# ATmegaIntOscillator.net
KiCad netlist of a schematic drawn in EAGLE
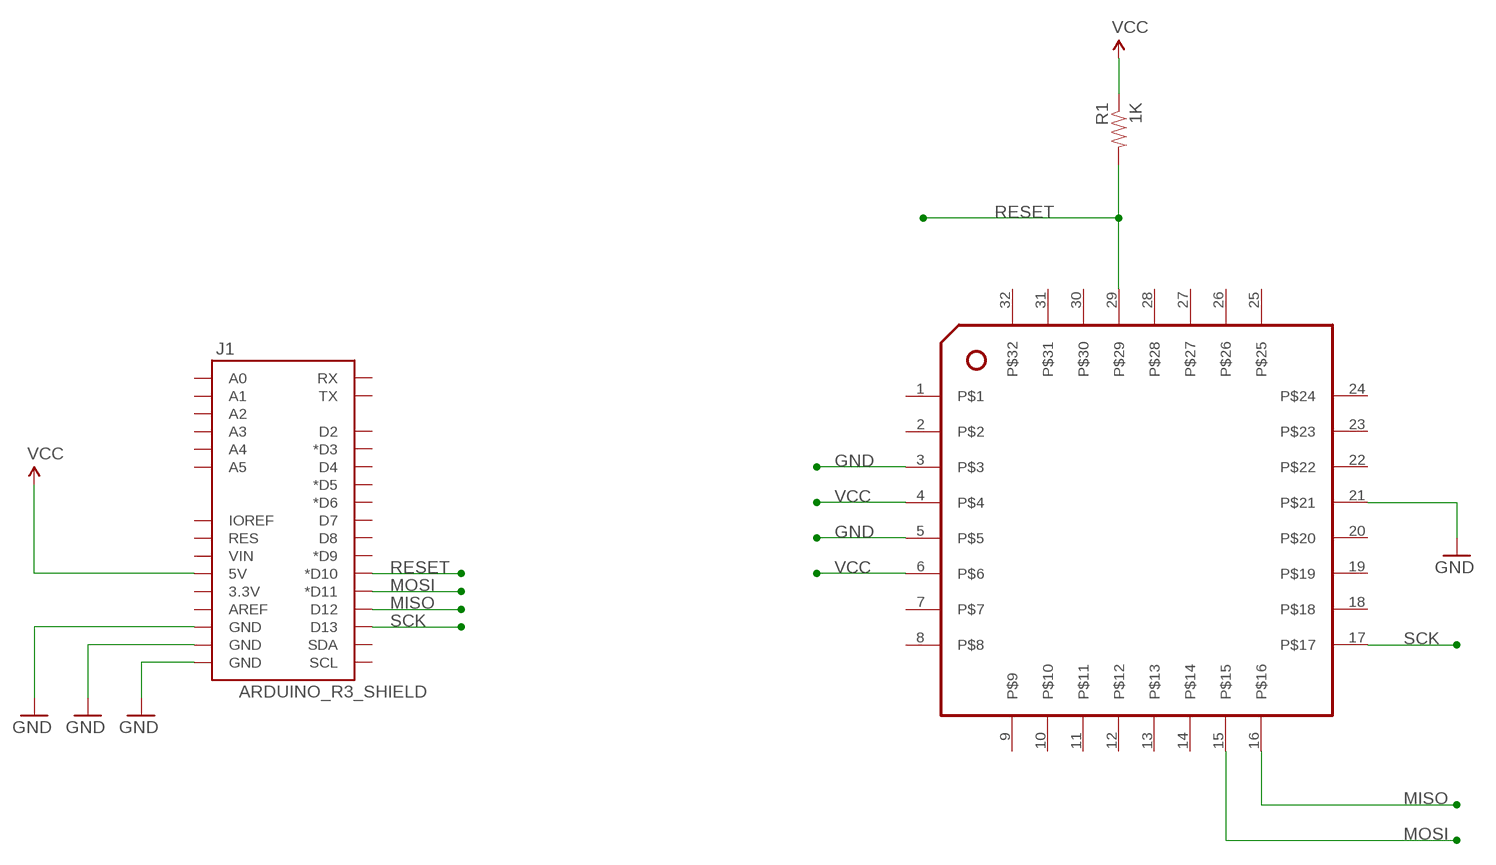
[diagram p0: schematic, sheet 1]

(export (version "E")
  (design (tool "Eeschema 10.0.6"))
  (components
    (comp (ref "J1")
      (value "ARDUINO_R3_SHIELD")
      (footprint "eagle-import:UNO_R3_SHIELD")
      (libsource (lib "eagle-import") (part "ARDUINO_R3_SHIELD"))
    )
    (comp (ref "R1")
      (value "1K")
      (footprint "eagle-import:AXIAL-0.3")
      (libsource (lib "eagle-import") (part "1KOHM-1/4W-1%(PTH)"))
    )
    (comp (ref "U$1")
      (value "ATMEGA-TQFP-BREAKOUT")
      (footprint "eagle-import:TQFP32-BREAKOUT")
      (libsource (lib "eagle-import") (part "ATMEGA-TQFP-BREAKOUT"))
    )
  )
  (nets
    (net (code "1") (name "/MISO") (class "Default")
      (node (ref "J1") (pin "D12") (pinfunction "D12_D12") (pintype "bidirectional"))
      (node (ref "U$1") (pin "16") (pinfunction "P$16_16") (pintype "bidirectional"))
    )
    (net (code "2") (name "/MOSI") (class "Default")
      (node (ref "J1") (pin "D11") (pinfunction "*D11_D11") (pintype "bidirectional"))
      (node (ref "U$1") (pin "15") (pinfunction "P$15_15") (pintype "bidirectional"))
    )
    (net (code "3") (name "/RESET") (class "Default")
      (node (ref "J1") (pin "D10") (pinfunction "*D10_D10") (pintype "bidirectional"))
      (node (ref "R1") (pin "P$2") (pinfunction "2_P$2") (pintype "passive"))
      (node (ref "U$1") (pin "29") (pinfunction "P$29_29") (pintype "bidirectional"))
    )
    (net (code "4") (name "/SCK") (class "Default")
      (node (ref "J1") (pin "D13") (pinfunction "D13_D13") (pintype "bidirectional"))
      (node (ref "U$1") (pin "17") (pinfunction "P$17_17") (pintype "bidirectional"))
    )
    (net (code "5") (name "GND") (class "Default")
      (node (ref "J1") (pin "GND@0") (pinfunction "GND_GND@0") (pintype "bidirectional"))
      (node (ref "J1") (pin "GND@1") (pinfunction "GND_GND@1") (pintype "bidirectional"))
      (node (ref "J1") (pin "GND@2") (pinfunction "GND_GND@2") (pintype "bidirectional"))
      (node (ref "U$1") (pin "21") (pinfunction "P$21_21") (pintype "bidirectional"))
      (node (ref "U$1") (pin "3") (pinfunction "P$3_3") (pintype "bidirectional"))
      (node (ref "U$1") (pin "5") (pinfunction "P$5_5") (pintype "bidirectional"))
    )
    (net (code "6") (name "VCC") (class "Default")
      (node (ref "J1") (pin "5V") (pinfunction "5V_5V") (pintype "bidirectional"))
      (node (ref "R1") (pin "P$1") (pinfunction "1_P$1") (pintype "passive"))
      (node (ref "U$1") (pin "4") (pinfunction "P$4_4") (pintype "bidirectional"))
      (node (ref "U$1") (pin "6") (pinfunction "P$6_6") (pintype "bidirectional"))
    )
    (net (code "7") (name "unconnected-(J1-*D3-PadD3)") (class "Default")
      (node (ref "J1") (pin "D3") (pinfunction "*D3_D3") (pintype "bidirectional"))
    )
    (net (code "8") (name "unconnected-(J1-*D5-PadD5)") (class "Default")
      (node (ref "J1") (pin "D5") (pinfunction "*D5_D5") (pintype "bidirectional"))
    )
    (net (code "9") (name "unconnected-(J1-*D6-PadD6)") (class "Default")
      (node (ref "J1") (pin "D6") (pinfunction "*D6_D6") (pintype "bidirectional"))
    )
    (net (code "10") (name "unconnected-(J1-*D9-PadD9)") (class "Default")
      (node (ref "J1") (pin "D9") (pinfunction "*D9_D9") (pintype "bidirectional"))
    )
    (net (code "11") (name "unconnected-(J1-Pad3.3V)") (class "Default")
      (node (ref "J1") (pin "3.3V") (pinfunction "3.3V_3.3V") (pintype "bidirectional"))
    )
    (net (code "12") (name "unconnected-(J1-PadA0)") (class "Default")
      (node (ref "J1") (pin "A0") (pinfunction "A0_A0") (pintype "bidirectional"))
    )
    (net (code "13") (name "unconnected-(J1-PadA1)") (class "Default")
      (node (ref "J1") (pin "A1") (pinfunction "A1_A1") (pintype "bidirectional"))
    )
    (net (code "14") (name "unconnected-(J1-PadA2)") (class "Default")
      (node (ref "J1") (pin "A2") (pinfunction "A2_A2") (pintype "bidirectional"))
    )
    (net (code "15") (name "unconnected-(J1-PadA3)") (class "Default")
      (node (ref "J1") (pin "A3") (pinfunction "A3_A3") (pintype "bidirectional"))
    )
    (net (code "16") (name "unconnected-(J1-PadA4)") (class "Default")
      (node (ref "J1") (pin "A4") (pinfunction "A4_A4") (pintype "bidirectional"))
    )
    (net (code "17") (name "unconnected-(J1-PadA5)") (class "Default")
      (node (ref "J1") (pin "A5") (pinfunction "A5_A5") (pintype "bidirectional"))
    )
    (net (code "18") (name "unconnected-(J1-PadAREF)") (class "Default")
      (node (ref "J1") (pin "AREF") (pinfunction "AREF_AREF") (pintype "bidirectional"))
    )
    (net (code "19") (name "unconnected-(J1-PadD2)") (class "Default")
      (node (ref "J1") (pin "D2") (pinfunction "D2_D2") (pintype "bidirectional"))
    )
    (net (code "20") (name "unconnected-(J1-PadD4)") (class "Default")
      (node (ref "J1") (pin "D4") (pinfunction "D4_D4") (pintype "bidirectional"))
    )
    (net (code "21") (name "unconnected-(J1-PadD7)") (class "Default")
      (node (ref "J1") (pin "D7") (pinfunction "D7_D7") (pintype "bidirectional"))
    )
    (net (code "22") (name "unconnected-(J1-PadD8)") (class "Default")
      (node (ref "J1") (pin "D8") (pinfunction "D8_D8") (pintype "bidirectional"))
    )
    (net (code "23") (name "unconnected-(J1-PadIOREF)") (class "Default")
      (node (ref "J1") (pin "IOREF") (pinfunction "IOREF_IOREF") (pintype "bidirectional"))
    )
    (net (code "24") (name "unconnected-(J1-PadRES)") (class "Default")
      (node (ref "J1") (pin "RES") (pinfunction "RES_RES") (pintype "bidirectional"))
    )
    (net (code "25") (name "unconnected-(J1-PadRX)") (class "Default")
      (node (ref "J1") (pin "RX") (pinfunction "RX_RX") (pintype "bidirectional"))
    )
    (net (code "26") (name "unconnected-(J1-PadSCL)") (class "Default")
      (node (ref "J1") (pin "SCL") (pinfunction "SCL_SCL") (pintype "bidirectional"))
    )
    (net (code "27") (name "unconnected-(J1-PadSDA)") (class "Default")
      (node (ref "J1") (pin "SDA") (pinfunction "SDA_SDA") (pintype "bidirectional"))
    )
    (net (code "28") (name "unconnected-(J1-PadTX)") (class "Default")
      (node (ref "J1") (pin "TX") (pinfunction "TX_TX") (pintype "bidirectional"))
    )
    (net (code "29") (name "unconnected-(J1-PadVIN)") (class "Default")
      (node (ref "J1") (pin "VIN") (pinfunction "VIN_VIN") (pintype "bidirectional"))
    )
    (net (code "30") (name "unconnected-(U$1-P$1-Pad1)") (class "Default")
      (node (ref "U$1") (pin "1") (pinfunction "P$1_1") (pintype "bidirectional"))
    )
    (net (code "31") (name "unconnected-(U$1-P$2-Pad2)") (class "Default")
      (node (ref "U$1") (pin "2") (pinfunction "P$2_2") (pintype "bidirectional"))
    )
    (net (code "32") (name "unconnected-(U$1-P$7-Pad7)") (class "Default")
      (node (ref "U$1") (pin "7") (pinfunction "P$7_7") (pintype "bidirectional"))
    )
    (net (code "33") (name "unconnected-(U$1-P$8-Pad8)") (class "Default")
      (node (ref "U$1") (pin "8") (pinfunction "P$8_8") (pintype "bidirectional"))
    )
    (net (code "34") (name "unconnected-(U$1-P$9-Pad9)") (class "Default")
      (node (ref "U$1") (pin "9") (pinfunction "P$9_9") (pintype "bidirectional"))
    )
    (net (code "35") (name "unconnected-(U$1-P$10-Pad10)") (class "Default")
      (node (ref "U$1") (pin "10") (pinfunction "P$10_10") (pintype "bidirectional"))
    )
    (net (code "36") (name "unconnected-(U$1-P$11-Pad11)") (class "Default")
      (node (ref "U$1") (pin "11") (pinfunction "P$11_11") (pintype "bidirectional"))
    )
    (net (code "37") (name "unconnected-(U$1-P$12-Pad12)") (class "Default")
      (node (ref "U$1") (pin "12") (pinfunction "P$12_12") (pintype "bidirectional"))
    )
    (net (code "38") (name "unconnected-(U$1-P$13-Pad13)") (class "Default")
      (node (ref "U$1") (pin "13") (pinfunction "P$13_13") (pintype "bidirectional"))
    )
    (net (code "39") (name "unconnected-(U$1-P$14-Pad14)") (class "Default")
      (node (ref "U$1") (pin "14") (pinfunction "P$14_14") (pintype "bidirectional"))
    )
    (net (code "40") (name "unconnected-(U$1-P$18-Pad18)") (class "Default")
      (node (ref "U$1") (pin "18") (pinfunction "P$18_18") (pintype "bidirectional"))
    )
    (net (code "41") (name "unconnected-(U$1-P$19-Pad19)") (class "Default")
      (node (ref "U$1") (pin "19") (pinfunction "P$19_19") (pintype "bidirectional"))
    )
    (net (code "42") (name "unconnected-(U$1-P$20-Pad20)") (class "Default")
      (node (ref "U$1") (pin "20") (pinfunction "P$20_20") (pintype "bidirectional"))
    )
    (net (code "43") (name "unconnected-(U$1-P$22-Pad22)") (class "Default")
      (node (ref "U$1") (pin "22") (pinfunction "P$22_22") (pintype "bidirectional"))
    )
    (net (code "44") (name "unconnected-(U$1-P$23-Pad23)") (class "Default")
      (node (ref "U$1") (pin "23") (pinfunction "P$23_23") (pintype "bidirectional"))
    )
    (net (code "45") (name "unconnected-(U$1-P$24-Pad24)") (class "Default")
      (node (ref "U$1") (pin "24") (pinfunction "P$24_24") (pintype "bidirectional"))
    )
    (net (code "46") (name "unconnected-(U$1-P$25-Pad25)") (class "Default")
      (node (ref "U$1") (pin "25") (pinfunction "P$25_25") (pintype "bidirectional"))
    )
    (net (code "47") (name "unconnected-(U$1-P$26-Pad26)") (class "Default")
      (node (ref "U$1") (pin "26") (pinfunction "P$26_26") (pintype "bidirectional"))
    )
    (net (code "48") (name "unconnected-(U$1-P$27-Pad27)") (class "Default")
      (node (ref "U$1") (pin "27") (pinfunction "P$27_27") (pintype "bidirectional"))
    )
    (net (code "49") (name "unconnected-(U$1-P$28-Pad28)") (class "Default")
      (node (ref "U$1") (pin "28") (pinfunction "P$28_28") (pintype "bidirectional"))
    )
    (net (code "50") (name "unconnected-(U$1-P$30-Pad30)") (class "Default")
      (node (ref "U$1") (pin "30") (pinfunction "P$30_30") (pintype "bidirectional"))
    )
    (net (code "51") (name "unconnected-(U$1-P$31-Pad31)") (class "Default")
      (node (ref "U$1") (pin "31") (pinfunction "P$31_31") (pintype "bidirectional"))
    )
    (net (code "52") (name "unconnected-(U$1-P$32-Pad32)") (class "Default")
      (node (ref "U$1") (pin "32") (pinfunction "P$32_32") (pintype "bidirectional"))
    )
  )
)
